# ShaqJr-BOTTOM.net
KiCad netlist of a schematic drawn in EAGLE
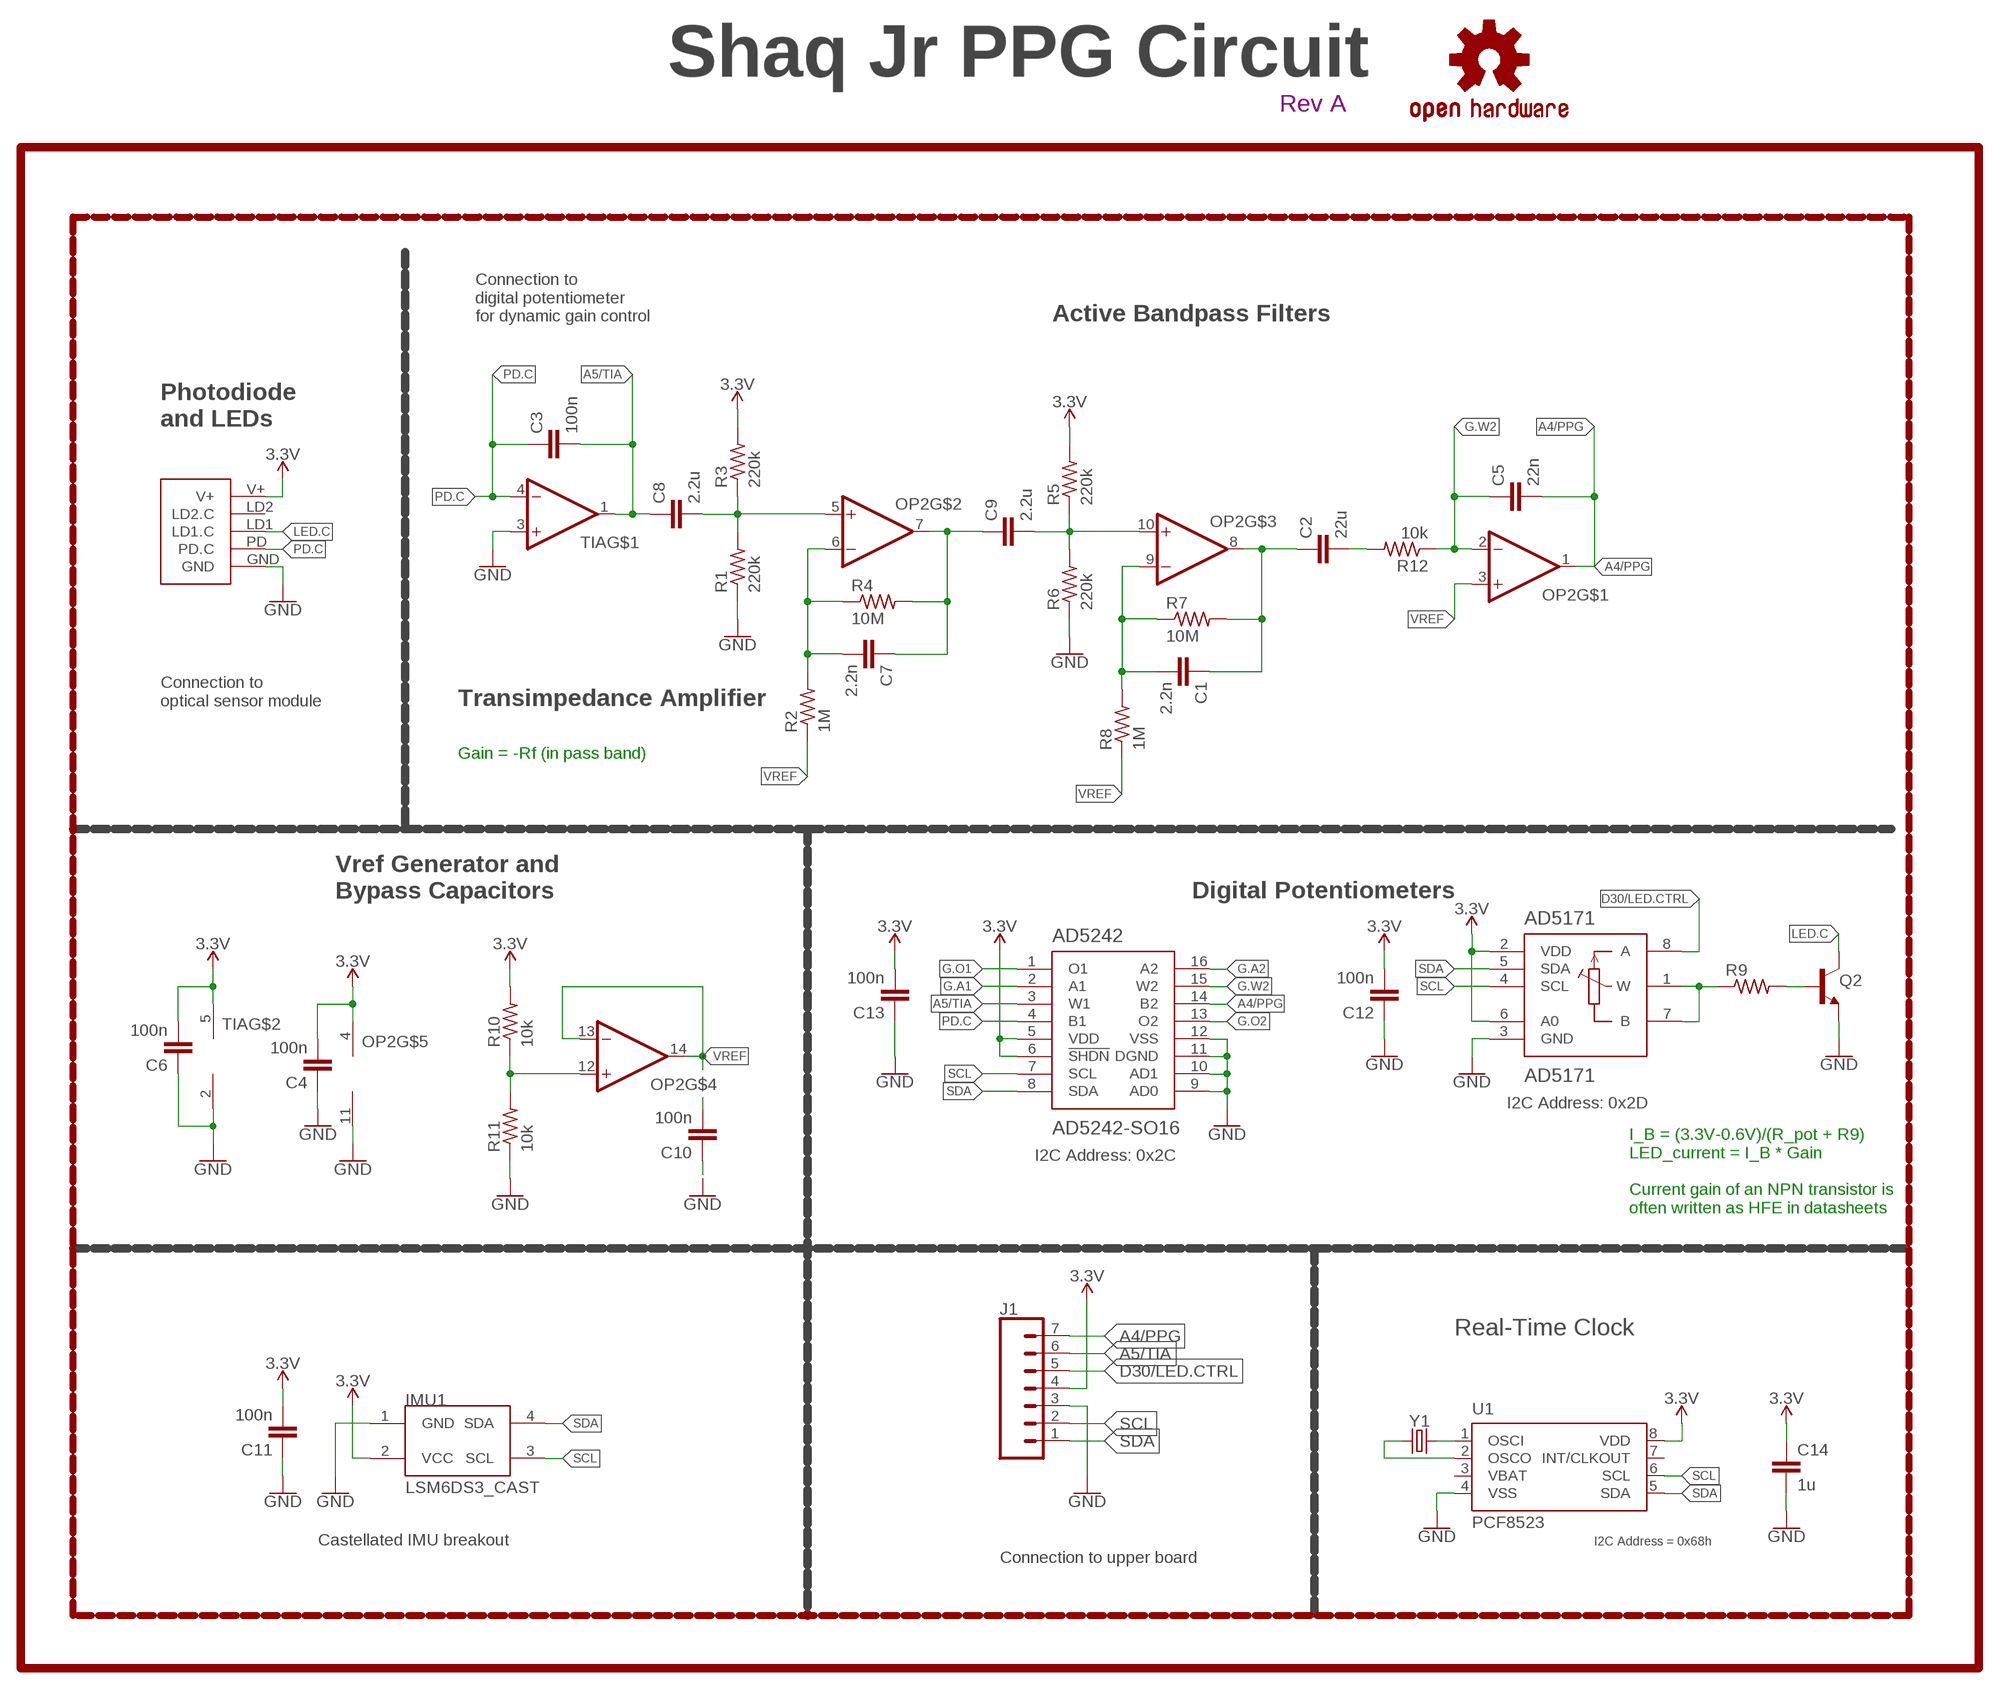
[diagram p0: schematic, sheet 1]

(export (version "E")
  (design (tool "Eeschema 10.0.6"))
  (components
    (comp (ref "AD5171")
      (value "AD5171")
      (footprint "eagle-import:SOT-23-8")
      (libsource (lib "eagle-import") (part "AD5171"))
    )
    (comp (ref "AD5242")
      (value "AD5242-SO16")
      (footprint "eagle-import:SO16")
      (libsource (lib "eagle-import") (part "AD5242-SO16"))
    )
    (comp (ref "C1")
      (value "2.2n")
      (footprint "eagle-import:C0603")
      (libsource (lib "eagle-import") (part "CAPACITOR0603"))
    )
    (comp (ref "C2")
      (value "22u")
      (footprint "eagle-import:C0603")
      (libsource (lib "eagle-import") (part "CAPACITOR0603"))
    )
    (comp (ref "C3")
      (value "100n")
      (footprint "eagle-import:C0603")
      (libsource (lib "eagle-import") (part "CAPACITOR0603"))
    )
    (comp (ref "C4")
      (value "100n")
      (footprint "eagle-import:C0603")
      (libsource (lib "eagle-import") (part "CAPACITOR0603"))
    )
    (comp (ref "C5")
      (value "22n")
      (footprint "eagle-import:C0603")
      (libsource (lib "eagle-import") (part "CAPACITOR0603"))
    )
    (comp (ref "C6")
      (value "100n")
      (footprint "eagle-import:C0603")
      (libsource (lib "eagle-import") (part "CAPACITOR0603"))
    )
    (comp (ref "C7")
      (value "2.2n")
      (footprint "eagle-import:C0603")
      (libsource (lib "eagle-import") (part "CAPACITOR0603"))
    )
    (comp (ref "C8")
      (value "2.2u")
      (footprint "eagle-import:C0603")
      (libsource (lib "eagle-import") (part "CAPACITOR0603"))
    )
    (comp (ref "C9")
      (value "2.2u")
      (footprint "eagle-import:C0603")
      (libsource (lib "eagle-import") (part "CAPACITOR0603"))
    )
    (comp (ref "C10")
      (value "100n")
      (footprint "eagle-import:C0603")
      (libsource (lib "eagle-import") (part "CAPACITOR0603"))
    )
    (comp (ref "C11")
      (value "100n")
      (footprint "eagle-import:C0603")
      (libsource (lib "eagle-import") (part "CAPACITOR0603"))
    )
    (comp (ref "C12")
      (value "100n")
      (footprint "eagle-import:C0603")
      (libsource (lib "eagle-import") (part "CAPACITOR0603"))
    )
    (comp (ref "C13")
      (value "100n")
      (footprint "eagle-import:C0603")
      (libsource (lib "eagle-import") (part "CAPACITOR0603"))
    )
    (comp (ref "C14")
      (value "1u")
      (footprint "eagle-import:C0603")
      (libsource (lib "eagle-import") (part "CAPACITOR0603"))
    )
    (comp (ref "IMU1")
      (value "LSM6DS3_CAST")
      (footprint "eagle-import:LSM6DS3_CAST")
      (libsource (lib "eagle-import") (part "LSM6DS3_CAST"))
    )
    (comp (ref "J1")
      (value "CONN_07-1.27MM")
      (footprint "eagle-import:1X07_1.27MM")
      (libsource (lib "eagle-import") (part "CONN_07-1.27MM"))
    )
    (comp (ref "LOGO1")
      (value "REVISION.A")
      (footprint "eagle-import:REV.A")
      (libsource (lib "eagle-import") (part "REVISION.A"))
    )
    (comp (ref "LOGO2")
      (value "OSHW-LOGOS")
      (footprint "eagle-import:OSHW-LOGO-S")
      (libsource (lib "eagle-import") (part "OSHW-LOGOS"))
    )
    (comp (ref "OP2")
      (value "OP-QUAD-SO14")
      (footprint "eagle-import:SO14")
      (libsource (lib "eagle-import") (part "OP-QUAD-SO14"))
    )
    (comp (ref "Q2")
      (value "NPN-GENERIC")
      (footprint "eagle-import:SOT23-3")
      (libsource (lib "eagle-import") (part "NPN-GENERIC"))
    )
    (comp (ref "R1")
      (value "220k")
      (footprint "eagle-import:R0603")
      (libsource (lib "eagle-import") (part "RESISTOR0603"))
    )
    (comp (ref "R2")
      (value "1M")
      (footprint "eagle-import:R0603")
      (libsource (lib "eagle-import") (part "RESISTOR0603"))
    )
    (comp (ref "R3")
      (value "220k")
      (footprint "eagle-import:R0603")
      (libsource (lib "eagle-import") (part "RESISTOR0603"))
    )
    (comp (ref "R4")
      (value "10M")
      (footprint "eagle-import:R0603")
      (libsource (lib "eagle-import") (part "RESISTOR0603"))
    )
    (comp (ref "R5")
      (value "220k")
      (footprint "eagle-import:R0603")
      (libsource (lib "eagle-import") (part "RESISTOR0603"))
    )
    (comp (ref "R6")
      (value "220k")
      (footprint "eagle-import:R0603")
      (libsource (lib "eagle-import") (part "RESISTOR0603"))
    )
    (comp (ref "R7")
      (value "10M")
      (footprint "eagle-import:R0603")
      (libsource (lib "eagle-import") (part "RESISTOR0603"))
    )
    (comp (ref "R8")
      (value "1M")
      (footprint "eagle-import:R0603")
      (libsource (lib "eagle-import") (part "RESISTOR0603"))
    )
    (comp (ref "R9")
      (value "RESISTOR0603")
      (footprint "eagle-import:R0603")
      (libsource (lib "eagle-import") (part "RESISTOR0603"))
    )
    (comp (ref "R10")
      (value "10k")
      (footprint "eagle-import:R0402")
      (libsource (lib "eagle-import") (part "RESISTOR0402"))
    )
    (comp (ref "R11")
      (value "10k")
      (footprint "eagle-import:R0402")
      (libsource (lib "eagle-import") (part "RESISTOR0402"))
    )
    (comp (ref "R12")
      (value "10k")
      (footprint "eagle-import:R0603")
      (libsource (lib "eagle-import") (part "RESISTOR0603"))
    )
    (comp (ref "TIA")
      (value "OP-SINGLEOT")
      (footprint "eagle-import:SOT23-5")
      (libsource (lib "eagle-import") (part "OP-SINGLEOT"))
    )
    (comp (ref "U$1")
      (value "PPG.MODULE.2")
      (footprint "eagle-import:PPG.MODULE.2")
      (libsource (lib "eagle-import") (part "PPG.MODULE.2"))
    )
    (comp (ref "U1")
      (value "PCF8523")
      (footprint "eagle-import:SO8")
      (fields
        (field (name "DIGIKEY") "568-5306-1-ND")
        (field (name "I2C_ADDRESS") "0x68h")
        (field (name "MFN") "PCF8523T/1,118")
        (field (name "MFN_MANUFACTURER") "NXP USA Inc.")
      )
      (libsource (lib "eagle-import") (part "PCF8523"))
    )
    (comp (ref "Y1")
      (value "32.7680kHz")
      (footprint "eagle-import:2-SMD.NOLEAD.2.0MMTO1.2MM")
      (fields (field (name "FREQ") "32.7680KHZ"))
      (libsource (lib "eagle-import") (part "CRYSTALECS-.327-12.5-12-C-TR"))
    )
  )
  (nets
    (net (code "1") (name "/VBAT") (class "Default")
      (node (ref "U1") (pin "3") (pinfunction "VBAT_3") (pintype "power_in"))
    )
    (net (code "2") (name "3.3V") (class "Default")
      (node (ref "AD5171") (pin "2") (pinfunction "VDD_2") (pintype "bidirectional"))
      (node (ref "AD5171") (pin "6") (pinfunction "A0_6") (pintype "bidirectional"))
      (node (ref "AD5242") (pin "5") (pinfunction "VDD_5") (pintype "bidirectional"))
      (node (ref "AD5242") (pin "6") (pinfunction "~{SHDN}_6") (pintype "bidirectional"))
      (node (ref "C11") (pin "2") (pinfunction "2_2") (pintype "passive"))
      (node (ref "C12") (pin "2") (pinfunction "2_2") (pintype "passive"))
      (node (ref "C13") (pin "2") (pinfunction "2_2") (pintype "passive"))
      (node (ref "C14") (pin "1") (pinfunction "1_1") (pintype "passive"))
      (node (ref "C4") (pin "2") (pinfunction "2_2") (pintype "passive"))
      (node (ref "C6") (pin "2") (pinfunction "2_2") (pintype "passive"))
      (node (ref "IMU1") (pin "2") (pinfunction "VCC_2") (pintype "bidirectional"))
      (node (ref "J1") (pin "4") (pinfunction "4_4") (pintype "passive"))
      (node (ref "OP2") (pin "4") (pinfunction "V+_4") (pintype "power_in"))
      (node (ref "R10") (pin "2") (pinfunction "2_2") (pintype "passive"))
      (node (ref "R3") (pin "2") (pinfunction "2_2") (pintype "passive"))
      (node (ref "R5") (pin "2") (pinfunction "2_2") (pintype "passive"))
      (node (ref "TIA") (pin "5") (pinfunction "V+_5") (pintype "power_in"))
      (node (ref "U$1") (pin "V+") (pinfunction "V+_V+") (pintype "bidirectional"))
      (node (ref "U1") (pin "8") (pinfunction "VDD_8") (pintype "power_in"))
    )
    (net (code "3") (name "A4{slash}PPG") (class "Default")
      (node (ref "AD5242") (pin "14") (pinfunction "B2_14") (pintype "bidirectional"))
      (node (ref "C5") (pin "2") (pinfunction "2_2") (pintype "passive"))
      (node (ref "J1") (pin "7") (pinfunction "7_7") (pintype "passive"))
      (node (ref "OP2") (pin "1") (pinfunction "OUT_1") (pintype "output"))
    )
    (net (code "4") (name "A5{slash}TIA") (class "Default")
      (node (ref "AD5242") (pin "3") (pinfunction "W1_3") (pintype "bidirectional"))
      (node (ref "C3") (pin "2") (pinfunction "2_2") (pintype "passive"))
      (node (ref "C8") (pin "1") (pinfunction "1_1") (pintype "passive"))
      (node (ref "J1") (pin "6") (pinfunction "6_6") (pintype "passive"))
      (node (ref "TIA") (pin "1") (pinfunction "OUT_1") (pintype "output"))
    )
    (net (code "5") (name "D30{slash}LED.CTRL") (class "Default")
      (node (ref "AD5171") (pin "8") (pinfunction "A_8") (pintype "bidirectional"))
      (node (ref "J1") (pin "5") (pinfunction "5_5") (pintype "passive"))
    )
    (net (code "6") (name "G.A1") (class "Default")
      (node (ref "AD5242") (pin "2") (pinfunction "A1_2") (pintype "bidirectional"))
    )
    (net (code "7") (name "G.A2") (class "Default")
      (node (ref "AD5242") (pin "16") (pinfunction "A2_16") (pintype "bidirectional"))
    )
    (net (code "8") (name "G.O1") (class "Default")
      (node (ref "AD5242") (pin "1") (pinfunction "O1_1") (pintype "bidirectional"))
    )
    (net (code "9") (name "G.O2") (class "Default")
      (node (ref "AD5242") (pin "13") (pinfunction "O2_13") (pintype "bidirectional"))
    )
    (net (code "10") (name "G.W2") (class "Default")
      (node (ref "AD5242") (pin "15") (pinfunction "W2_15") (pintype "bidirectional"))
      (node (ref "C5") (pin "1") (pinfunction "1_1") (pintype "passive"))
      (node (ref "OP2") (pin "2") (pinfunction "-IN_2") (pintype "input"))
      (node (ref "R12") (pin "1") (pinfunction "1_1") (pintype "passive"))
    )
    (net (code "11") (name "GND") (class "Default")
      (node (ref "AD5171") (pin "3") (pinfunction "GND_3") (pintype "bidirectional"))
      (node (ref "AD5242") (pin "10") (pinfunction "AD1_10") (pintype "bidirectional"))
      (node (ref "AD5242") (pin "11") (pinfunction "DGND_11") (pintype "bidirectional"))
      (node (ref "AD5242") (pin "12") (pinfunction "VSS_12") (pintype "bidirectional"))
      (node (ref "AD5242") (pin "9") (pinfunction "AD0_9") (pintype "bidirectional"))
      (node (ref "C10") (pin "1") (pinfunction "1_1") (pintype "passive"))
      (node (ref "C11") (pin "1") (pinfunction "1_1") (pintype "passive"))
      (node (ref "C12") (pin "1") (pinfunction "1_1") (pintype "passive"))
      (node (ref "C13") (pin "1") (pinfunction "1_1") (pintype "passive"))
      (node (ref "C14") (pin "2") (pinfunction "2_2") (pintype "passive"))
      (node (ref "C4") (pin "1") (pinfunction "1_1") (pintype "passive"))
      (node (ref "C6") (pin "1") (pinfunction "1_1") (pintype "passive"))
      (node (ref "IMU1") (pin "1") (pinfunction "GND_1") (pintype "bidirectional"))
      (node (ref "J1") (pin "3") (pinfunction "3_3") (pintype "passive"))
      (node (ref "OP2") (pin "11") (pinfunction "V-_11") (pintype "power_in"))
      (node (ref "Q2") (pin "2") (pinfunction "E_2") (pintype "passive"))
      (node (ref "R1") (pin "1") (pinfunction "1_1") (pintype "passive"))
      (node (ref "R11") (pin "1") (pinfunction "1_1") (pintype "passive"))
      (node (ref "R6") (pin "1") (pinfunction "1_1") (pintype "passive"))
      (node (ref "TIA") (pin "2") (pinfunction "V-_2") (pintype "power_in"))
      (node (ref "TIA") (pin "3") (pinfunction "+IN_3") (pintype "input"))
      (node (ref "U$1") (pin "GND") (pinfunction "GND_GND") (pintype "bidirectional"))
      (node (ref "U1") (pin "4") (pinfunction "VSS_4") (pintype "power_in"))
    )
    (net (code "12") (name "LED.C") (class "Default")
      (node (ref "Q2") (pin "3") (pinfunction "C_3") (pintype "passive"))
      (node (ref "U$1") (pin "LD1") (pinfunction "LD1.C_LD1") (pintype "bidirectional"))
    )
    (net (code "13") (name "Net-(AD5171-B)") (class "Default")
      (node (ref "AD5171") (pin "1") (pinfunction "W_1") (pintype "bidirectional"))
      (node (ref "AD5171") (pin "7") (pinfunction "B_7") (pintype "bidirectional"))
      (node (ref "R9") (pin "1") (pinfunction "1_1") (pintype "passive"))
    )
    (net (code "14") (name "Net-(C2-Pad2)") (class "Default")
      (node (ref "C2") (pin "2") (pinfunction "2_2") (pintype "passive"))
      (node (ref "R12") (pin "2") (pinfunction "2_2") (pintype "passive"))
    )
    (net (code "15") (name "Net-(OP2B-+IN)") (class "Default")
      (node (ref "C8") (pin "2") (pinfunction "2_2") (pintype "passive"))
      (node (ref "OP2") (pin "5") (pinfunction "+IN_5") (pintype "input"))
      (node (ref "R1") (pin "2") (pinfunction "2_2") (pintype "passive"))
      (node (ref "R3") (pin "1") (pinfunction "1_1") (pintype "passive"))
    )
    (net (code "16") (name "Net-(OP2B--IN)") (class "Default")
      (node (ref "C7") (pin "2") (pinfunction "2_2") (pintype "passive"))
      (node (ref "OP2") (pin "6") (pinfunction "-IN_6") (pintype "input"))
      (node (ref "R2") (pin "2") (pinfunction "2_2") (pintype "passive"))
      (node (ref "R4") (pin "1") (pinfunction "1_1") (pintype "passive"))
    )
    (net (code "17") (name "Net-(OP2B-OUT)") (class "Default")
      (node (ref "C7") (pin "1") (pinfunction "1_1") (pintype "passive"))
      (node (ref "C9") (pin "1") (pinfunction "1_1") (pintype "passive"))
      (node (ref "OP2") (pin "7") (pinfunction "OUT_7") (pintype "output"))
      (node (ref "R4") (pin "2") (pinfunction "2_2") (pintype "passive"))
    )
    (net (code "18") (name "Net-(OP2C-+IN)") (class "Default")
      (node (ref "C9") (pin "2") (pinfunction "2_2") (pintype "passive"))
      (node (ref "OP2") (pin "10") (pinfunction "+IN_10") (pintype "input"))
      (node (ref "R5") (pin "1") (pinfunction "1_1") (pintype "passive"))
      (node (ref "R6") (pin "2") (pinfunction "2_2") (pintype "passive"))
    )
    (net (code "19") (name "Net-(OP2C--IN)") (class "Default")
      (node (ref "C1") (pin "2") (pinfunction "2_2") (pintype "passive"))
      (node (ref "OP2") (pin "9") (pinfunction "-IN_9") (pintype "input"))
      (node (ref "R7") (pin "1") (pinfunction "1_1") (pintype "passive"))
      (node (ref "R8") (pin "2") (pinfunction "2_2") (pintype "passive"))
    )
    (net (code "20") (name "Net-(OP2C-OUT)") (class "Default")
      (node (ref "C1") (pin "1") (pinfunction "1_1") (pintype "passive"))
      (node (ref "C2") (pin "1") (pinfunction "1_1") (pintype "passive"))
      (node (ref "OP2") (pin "8") (pinfunction "OUT_8") (pintype "output"))
      (node (ref "R7") (pin "2") (pinfunction "2_2") (pintype "passive"))
    )
    (net (code "21") (name "Net-(OP2D-+IN)") (class "Default")
      (node (ref "OP2") (pin "12") (pinfunction "+IN_12") (pintype "input"))
      (node (ref "R10") (pin "1") (pinfunction "1_1") (pintype "passive"))
      (node (ref "R11") (pin "2") (pinfunction "2_2") (pintype "passive"))
    )
    (net (code "22") (name "Net-(Q2-B)") (class "Default")
      (node (ref "Q2") (pin "1") (pinfunction "B_1") (pintype "passive"))
      (node (ref "R9") (pin "2") (pinfunction "2_2") (pintype "passive"))
    )
    (net (code "23") (name "Net-(U1-OSCI)") (class "Default")
      (node (ref "U1") (pin "1") (pinfunction "OSCI_1") (pintype "bidirectional"))
      (node (ref "Y1") (pin "P$2") (pinfunction "2_P$2") (pintype "passive"))
    )
    (net (code "24") (name "Net-(U1-OSCO)") (class "Default")
      (node (ref "U1") (pin "2") (pinfunction "OSCO_2") (pintype "bidirectional"))
      (node (ref "Y1") (pin "P$1") (pinfunction "1_P$1") (pintype "passive"))
    )
    (net (code "25") (name "PD.C") (class "Default")
      (node (ref "AD5242") (pin "4") (pinfunction "B1_4") (pintype "bidirectional"))
      (node (ref "C3") (pin "1") (pinfunction "1_1") (pintype "passive"))
      (node (ref "TIA") (pin "4") (pinfunction "-IN_4") (pintype "input"))
      (node (ref "U$1") (pin "PD") (pinfunction "PD.C_PD") (pintype "bidirectional"))
    )
    (net (code "26") (name "SCL") (class "Default")
      (node (ref "AD5171") (pin "4") (pinfunction "SCL_4") (pintype "bidirectional"))
      (node (ref "AD5242") (pin "7") (pinfunction "SCL_7") (pintype "bidirectional"))
      (node (ref "IMU1") (pin "3") (pinfunction "SCL_3") (pintype "bidirectional"))
      (node (ref "J1") (pin "2") (pinfunction "2_2") (pintype "passive"))
      (node (ref "U1") (pin "6") (pinfunction "SCL_6") (pintype "bidirectional"))
    )
    (net (code "27") (name "SDA") (class "Default")
      (node (ref "AD5171") (pin "5") (pinfunction "SDA_5") (pintype "bidirectional"))
      (node (ref "AD5242") (pin "8") (pinfunction "SDA_8") (pintype "bidirectional"))
      (node (ref "IMU1") (pin "4") (pinfunction "SDA_4") (pintype "bidirectional"))
      (node (ref "J1") (pin "1") (pinfunction "1_1") (pintype "passive"))
      (node (ref "U1") (pin "5") (pinfunction "SDA_5") (pintype "bidirectional"))
    )
    (net (code "28") (name "VREF") (class "Default")
      (node (ref "C10") (pin "2") (pinfunction "2_2") (pintype "passive"))
      (node (ref "OP2") (pin "13") (pinfunction "-IN_13") (pintype "input"))
      (node (ref "OP2") (pin "14") (pinfunction "OUT_14") (pintype "output"))
      (node (ref "OP2") (pin "3") (pinfunction "+IN_3") (pintype "input"))
      (node (ref "R2") (pin "1") (pinfunction "1_1") (pintype "passive"))
      (node (ref "R8") (pin "1") (pinfunction "1_1") (pintype "passive"))
    )
    (net (code "29") (name "unconnected-(U$1-LD2.C-PadLD2)") (class "Default")
      (node (ref "U$1") (pin "LD2") (pinfunction "LD2.C_LD2") (pintype "bidirectional"))
    )
    (net (code "30") (name "unconnected-(U1-INT{slash}CLKOUT-Pad7)") (class "Default")
      (node (ref "U1") (pin "7") (pinfunction "INT/CLKOUT_7") (pintype "bidirectional"))
    )
  )
)
